# mapleCUx_large_226.net
KiCad netlist of a schematic drawn in EAGLE
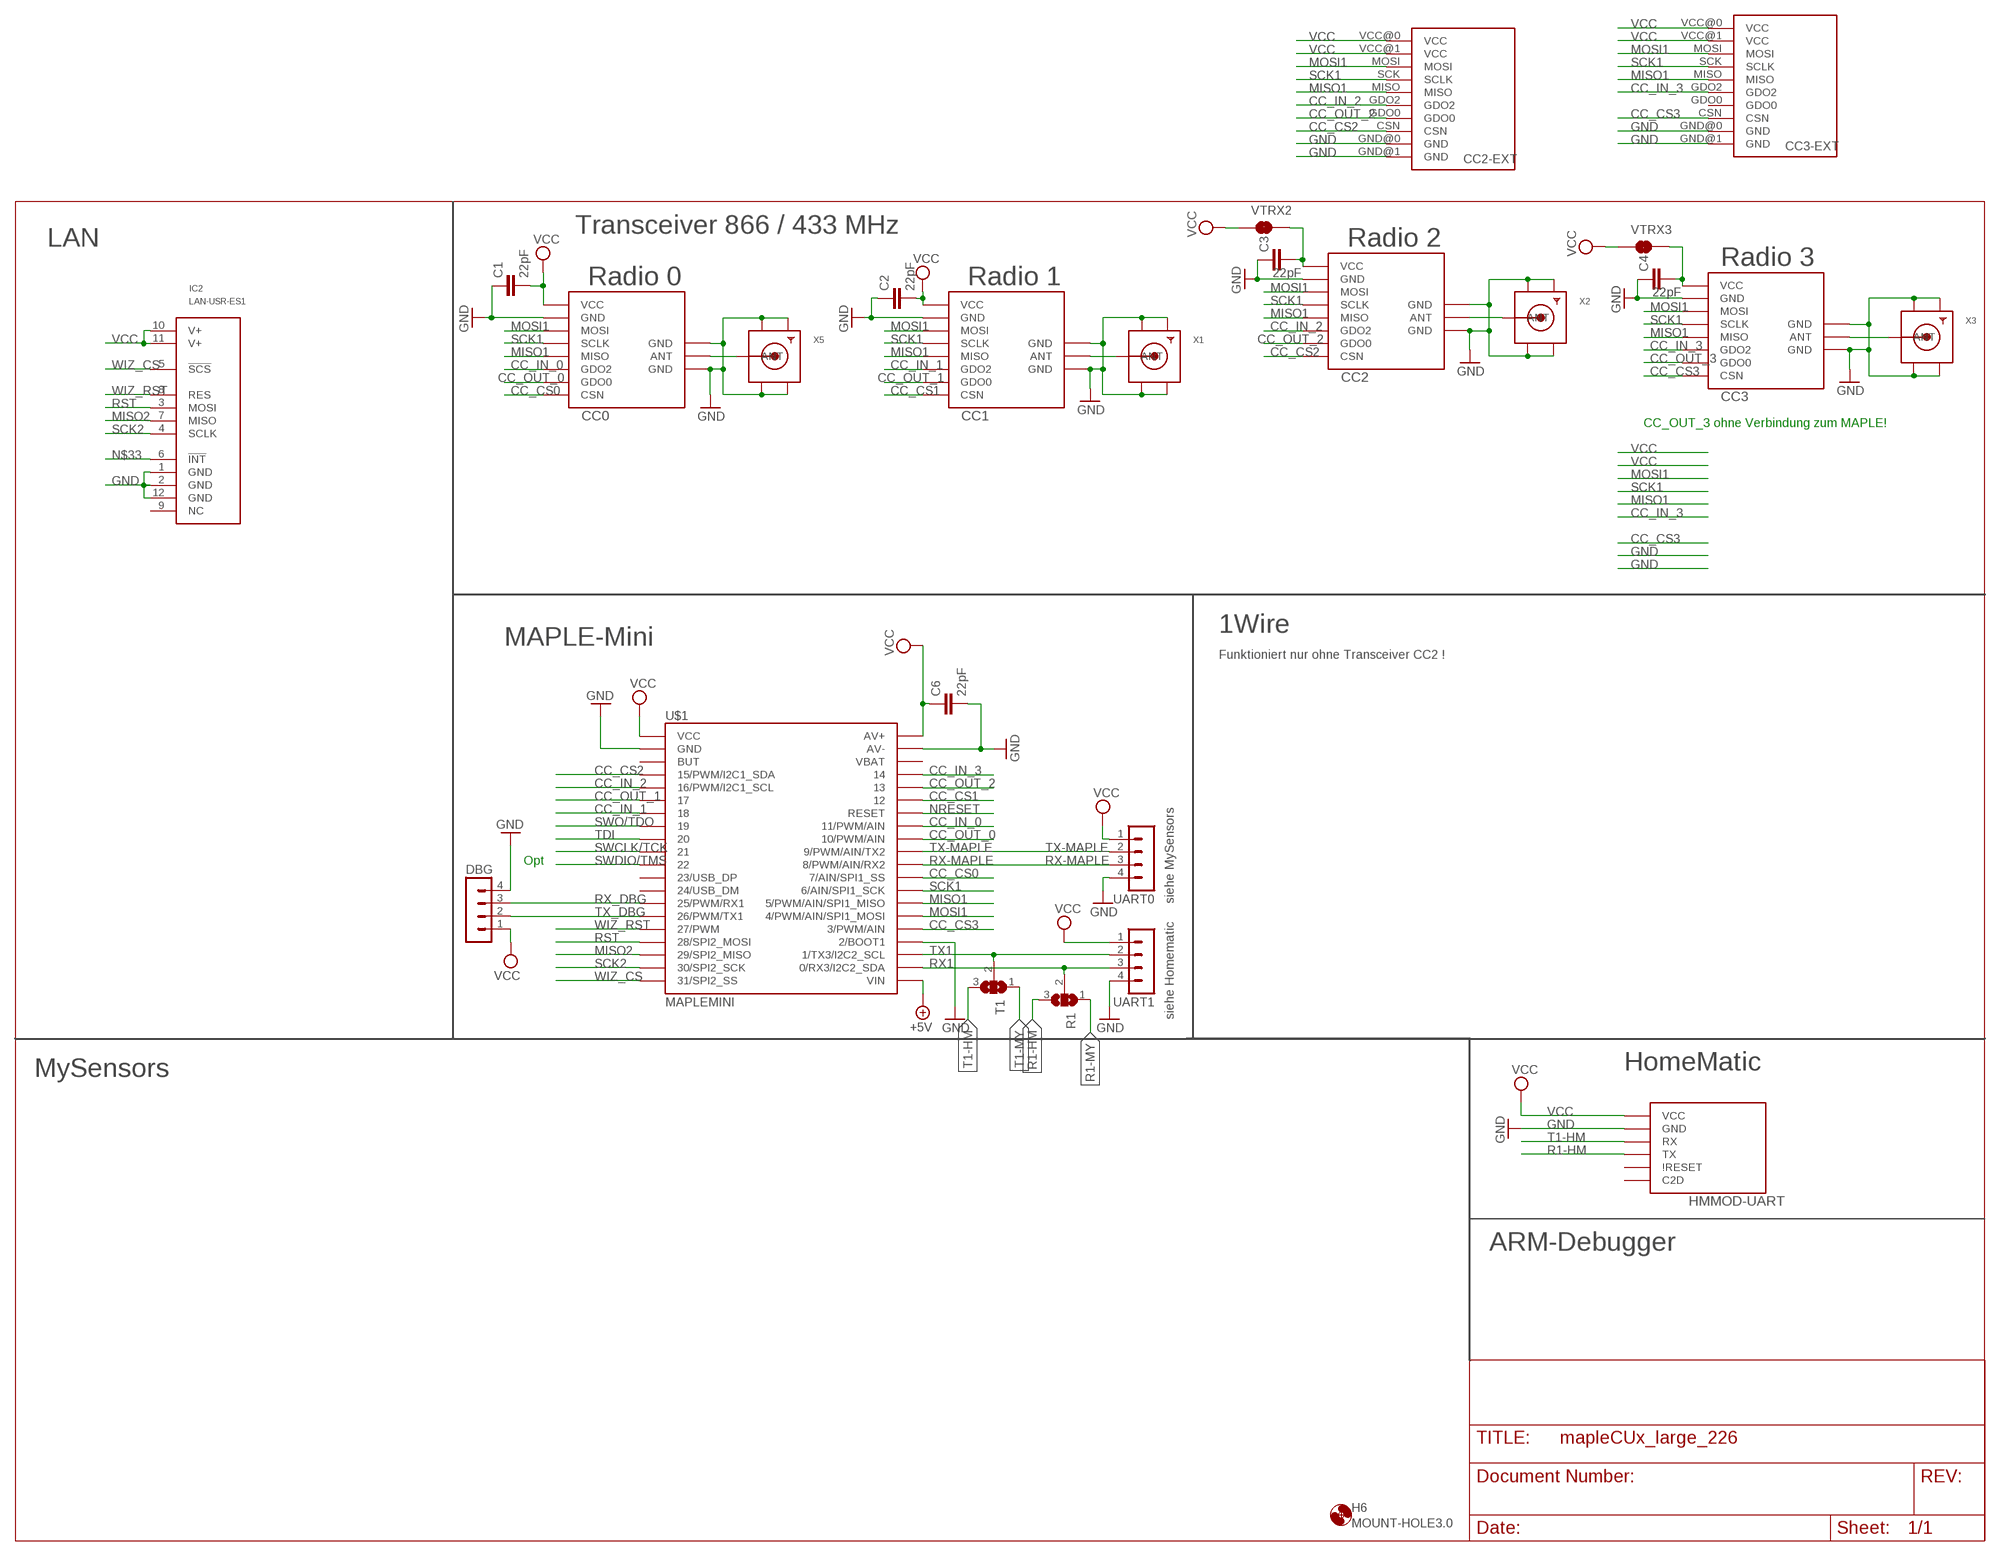
[diagram p0: schematic, sheet 1]

(export (version "E")
  (design (tool "Eeschema 10.0.6"))
  (components
    (comp (ref "C1")
      (value "22pF")
      (footprint "eagle-import:C0805")
      (libsource (lib "eagle-import") (part "C-EUC0805"))
    )
    (comp (ref "C2")
      (value "22pF")
      (footprint "eagle-import:C0805")
      (libsource (lib "eagle-import") (part "C-EUC0805"))
    )
    (comp (ref "C3")
      (value "22pF")
      (footprint "eagle-import:C0805")
      (libsource (lib "eagle-import") (part "C-EUC0805"))
    )
    (comp (ref "C4")
      (value "22pF")
      (footprint "eagle-import:C0805")
      (libsource (lib "eagle-import") (part "C-EUC0805"))
    )
    (comp (ref "C6")
      (value "22pF")
      (footprint "eagle-import:C0805")
      (libsource (lib "eagle-import") (part "C-EUC0805"))
    )
    (comp (ref "CC0")
      (value "CC1101")
      (footprint "eagle-import:CC1101_MODULE1_SMD")
      (libsource (lib "eagle-import") (part "CC1101_MODULE1SMD"))
    )
    (comp (ref "CC1")
      (value "CC1101_MODULE1SMD")
      (footprint "eagle-import:CC1101_MODULE1_SMD")
      (libsource (lib "eagle-import") (part "CC1101_MODULE1SMD"))
    )
    (comp (ref "CC2")
      (value "CC1101_MODULE1SMD")
      (footprint "eagle-import:CC1101_MODULE1_SMD")
      (libsource (lib "eagle-import") (part "CC1101_MODULE1SMD"))
    )
    (comp (ref "CC2-EXT")
      (value "CC1101_MODULE3_DIL")
      (footprint "eagle-import:CC1101_MODULE3_DIL")
      (libsource (lib "eagle-import") (part "CC1101_MODULE3_DIL"))
    )
    (comp (ref "CC3")
      (value "CC1101_MODULE1SMD")
      (footprint "eagle-import:CC1101_MODULE1_SMD")
      (libsource (lib "eagle-import") (part "CC1101_MODULE1SMD"))
    )
    (comp (ref "CC3-EXT")
      (value "CC1101_MODULE3_DIL")
      (footprint "eagle-import:CC1101_MODULE3_DIL")
      (libsource (lib "eagle-import") (part "CC1101_MODULE3_DIL"))
    )
    (comp (ref "DBG")
      (value "MA04-1")
      (footprint "eagle-import:MA04-1")
      (libsource (lib "eagle-import") (part "MA04-1"))
    )
    (comp (ref "H6")
      (value "MOUNT-HOLE3.0")
      (footprint "eagle-import:3,0")
      (libsource (lib "eagle-import") (part "MOUNT-HOLE3.0"))
    )
    (comp (ref "HMMOD-UART")
      (value "HM-MOD-UARTDIL")
      (footprint "eagle-import:HM-MOD-UART-DIL")
      (libsource (lib "eagle-import") (part "HM-MOD-UARTDIL"))
    )
    (comp (ref "IC2")
      (value "LAN-USR-ES1")
      (footprint "eagle-import:USR-ES1")
      (libsource (lib "eagle-import") (part "LAN-USR-ES1"))
    )
    (comp (ref "R1")
      (value "SJ2W")
      (footprint "eagle-import:SJ_2")
      (libsource (lib "eagle-import") (part "SJ2W"))
    )
    (comp (ref "T1")
      (value "SJ2W")
      (footprint "eagle-import:SJ_2")
      (libsource (lib "eagle-import") (part "SJ2W"))
    )
    (comp (ref "U$1")
      (value "MAPLEMINI")
      (footprint "eagle-import:20-DIP")
      (libsource (lib "eagle-import") (part "MAPLEMINI"))
    )
    (comp (ref "UART0")
      (value "MA04-1")
      (footprint "eagle-import:MA04-1")
      (libsource (lib "eagle-import") (part "MA04-1"))
    )
    (comp (ref "UART1")
      (value "MA04-1")
      (footprint "eagle-import:MA04-1")
      (libsource (lib "eagle-import") (part "MA04-1"))
    )
    (comp (ref "VTRX2")
      (value "JUMPER-SMT_2_NC_TRACE_SILK")
      (footprint "eagle-import:SMT-JUMPER_2_NC_TRACE_SILK")
      (libsource (lib "eagle-import") (part "JUMPER-SMT_2_NC_TRACE_SILK"))
    )
    (comp (ref "VTRX3")
      (value "JUMPER-SMT_2_NC_TRACE_SILK")
      (footprint "eagle-import:SMT-JUMPER_2_NC_TRACE_SILK")
      (libsource (lib "eagle-import") (part "JUMPER-SMT_2_NC_TRACE_SILK"))
    )
    (comp (ref "X1")
      (value "SMACONNECTOR_EDGE")
      (footprint "eagle-import:SMA_EDGELAUNCH")
      (libsource (lib "eagle-import") (part "SMACONNECTOR_EDGE"))
    )
    (comp (ref "X2")
      (value "SMACONNECTOR_EDGE")
      (footprint "eagle-import:SMA_EDGELAUNCH")
      (libsource (lib "eagle-import") (part "SMACONNECTOR_EDGE"))
    )
    (comp (ref "X3")
      (value "SMACONNECTOR_EDGE")
      (footprint "eagle-import:SMA_EDGELAUNCH")
      (libsource (lib "eagle-import") (part "SMACONNECTOR_EDGE"))
    )
    (comp (ref "X5")
      (value "SMACONNECTOR_EDGE")
      (footprint "eagle-import:SMA_EDGELAUNCH")
      (libsource (lib "eagle-import") (part "SMACONNECTOR_EDGE"))
    )
  )
  (nets
    (net (code "1") (name "+5V") (class "Default")
      (node (ref "U$1") (pin "21") (pinfunction "VIN_21") (pintype "bidirectional"))
    )
    (net (code "2") (name "/CC_CS0") (class "Default")
      (node (ref "CC0") (pin "CSN") (pinfunction "CSN_CSN") (pintype "bidirectional"))
      (node (ref "U$1") (pin "29") (pinfunction "7/AIN/SPI1_SS_29") (pintype "bidirectional"))
    )
    (net (code "3") (name "/CC_CS1") (class "Default")
      (node (ref "CC1") (pin "CSN") (pinfunction "CSN_CSN") (pintype "bidirectional"))
      (node (ref "U$1") (pin "35") (pinfunction "12_35") (pintype "bidirectional"))
    )
    (net (code "4") (name "/CC_CS2") (class "Default")
      (node (ref "CC2") (pin "CSN") (pinfunction "CSN_CSN") (pintype "bidirectional"))
      (node (ref "CC2-EXT") (pin "CSN") (pinfunction "CSN_CSN") (pintype "bidirectional"))
      (node (ref "U$1") (pin "4") (pinfunction "15/PWM/I2C1_SDA_4") (pintype "bidirectional"))
    )
    (net (code "5") (name "/CC_CS3") (class "Default")
      (node (ref "CC3") (pin "CSN") (pinfunction "CSN_CSN") (pintype "bidirectional"))
      (node (ref "CC3-EXT") (pin "CSN") (pinfunction "CSN_CSN") (pintype "bidirectional"))
      (node (ref "U$1") (pin "25") (pinfunction "3/PWM/AIN_25") (pintype "bidirectional"))
    )
    (net (code "6") (name "/CC_IN_0") (class "Default")
      (node (ref "CC0") (pin "GDO2") (pinfunction "GDO2_GDO2") (pintype "bidirectional"))
      (node (ref "U$1") (pin "33") (pinfunction "11/PWM/AIN_33") (pintype "bidirectional"))
    )
    (net (code "7") (name "/CC_IN_1") (class "Default")
      (node (ref "CC1") (pin "GDO2") (pinfunction "GDO2_GDO2") (pintype "bidirectional"))
      (node (ref "U$1") (pin "7") (pinfunction "18_7") (pintype "bidirectional"))
    )
    (net (code "8") (name "/CC_IN_2") (class "Default")
      (node (ref "CC2") (pin "GDO2") (pinfunction "GDO2_GDO2") (pintype "bidirectional"))
      (node (ref "CC2-EXT") (pin "GDO2") (pinfunction "GDO2_GDO2") (pintype "bidirectional"))
      (node (ref "U$1") (pin "5") (pinfunction "16/PWM/I2C1_SCL_5") (pintype "bidirectional"))
    )
    (net (code "9") (name "/CC_IN_3") (class "Default")
      (node (ref "CC3") (pin "GDO2") (pinfunction "GDO2_GDO2") (pintype "bidirectional"))
      (node (ref "CC3-EXT") (pin "GDO2") (pinfunction "GDO2_GDO2") (pintype "bidirectional"))
      (node (ref "U$1") (pin "37") (pinfunction "14_37") (pintype "bidirectional"))
    )
    (net (code "10") (name "/CC_OUT_0") (class "Default")
      (node (ref "CC0") (pin "GDO0") (pinfunction "GDO0_GDO0") (pintype "bidirectional"))
      (node (ref "U$1") (pin "32") (pinfunction "10/PWM/AIN_32") (pintype "bidirectional"))
    )
    (net (code "11") (name "/CC_OUT_1") (class "Default")
      (node (ref "CC1") (pin "GDO0") (pinfunction "GDO0_GDO0") (pintype "bidirectional"))
      (node (ref "U$1") (pin "6") (pinfunction "17_6") (pintype "bidirectional"))
    )
    (net (code "12") (name "/CC_OUT_2") (class "Default")
      (node (ref "CC2") (pin "GDO0") (pinfunction "GDO0_GDO0") (pintype "bidirectional"))
      (node (ref "CC2-EXT") (pin "GDO0") (pinfunction "GDO0_GDO0") (pintype "bidirectional"))
      (node (ref "U$1") (pin "36") (pinfunction "13_36") (pintype "bidirectional"))
    )
    (net (code "13") (name "/CC_OUT_3") (class "Default")
      (node (ref "CC3") (pin "GDO0") (pinfunction "GDO0_GDO0") (pintype "bidirectional"))
    )
    (net (code "14") (name "/MISO1") (class "Default")
      (node (ref "CC0") (pin "MISO") (pinfunction "MISO_MISO") (pintype "bidirectional"))
      (node (ref "CC1") (pin "MISO") (pinfunction "MISO_MISO") (pintype "bidirectional"))
      (node (ref "CC2") (pin "MISO") (pinfunction "MISO_MISO") (pintype "bidirectional"))
      (node (ref "CC2-EXT") (pin "MISO") (pinfunction "MISO_MISO") (pintype "bidirectional"))
      (node (ref "CC3") (pin "MISO") (pinfunction "MISO_MISO") (pintype "bidirectional"))
      (node (ref "CC3-EXT") (pin "MISO") (pinfunction "MISO_MISO") (pintype "bidirectional"))
      (node (ref "U$1") (pin "27") (pinfunction "5/PWM/AIN/SPI1_MISO_27") (pintype "bidirectional"))
    )
    (net (code "15") (name "/MISO2") (class "Default")
      (node (ref "IC2") (pin "7") (pinfunction "MISO_7") (pintype "bidirectional"))
      (node (ref "U$1") (pin "18") (pinfunction "29/SPI2_MISO_18") (pintype "bidirectional"))
    )
    (net (code "16") (name "/MOSI1") (class "Default")
      (node (ref "CC0") (pin "MOSI") (pinfunction "MOSI_MOSI") (pintype "bidirectional"))
      (node (ref "CC1") (pin "MOSI") (pinfunction "MOSI_MOSI") (pintype "bidirectional"))
      (node (ref "CC2") (pin "MOSI") (pinfunction "MOSI_MOSI") (pintype "bidirectional"))
      (node (ref "CC2-EXT") (pin "MOSI") (pinfunction "MOSI_MOSI") (pintype "bidirectional"))
      (node (ref "CC3") (pin "MOSI") (pinfunction "MOSI_MOSI") (pintype "bidirectional"))
      (node (ref "CC3-EXT") (pin "MOSI") (pinfunction "MOSI_MOSI") (pintype "bidirectional"))
      (node (ref "U$1") (pin "26") (pinfunction "4/PWM/AIN/SPI1_MOSI_26") (pintype "bidirectional"))
    )
    (net (code "17") (name "/N$33") (class "Default")
      (node (ref "IC2") (pin "6") (pinfunction "~{INT}_6") (pintype "output"))
    )
    (net (code "18") (name "/NRESET") (class "Default")
      (node (ref "U$1") (pin "34") (pinfunction "RESET_34") (pintype "bidirectional"))
    )
    (net (code "19") (name "/RST") (class "Default")
      (node (ref "IC2") (pin "3") (pinfunction "MOSI_3") (pintype "bidirectional"))
      (node (ref "U$1") (pin "17") (pinfunction "28/SPI2_MOSI_17") (pintype "bidirectional"))
    )
    (net (code "20") (name "/RX-MAPLE") (class "Default")
      (node (ref "U$1") (pin "30") (pinfunction "8/PWM/AIN/RX2_30") (pintype "bidirectional"))
      (node (ref "UART0") (pin "3") (pinfunction "3_3") (pintype "passive"))
    )
    (net (code "21") (name "/RX1") (class "Default")
      (node (ref "R1") (pin "2") (pinfunction "2_2") (pintype "passive"))
      (node (ref "U$1") (pin "22") (pinfunction "0/RX3/I2C2_SDA_22") (pintype "bidirectional"))
      (node (ref "UART1") (pin "3") (pinfunction "3_3") (pintype "passive"))
    )
    (net (code "22") (name "/RX_DBG") (class "Default")
      (node (ref "DBG") (pin "3") (pinfunction "3_3") (pintype "passive"))
      (node (ref "U$1") (pin "14") (pinfunction "25/PWM/RX1_14") (pintype "bidirectional"))
    )
    (net (code "23") (name "/SCK1") (class "Default")
      (node (ref "CC0") (pin "SCLK") (pinfunction "SCLK_SCLK") (pintype "bidirectional"))
      (node (ref "CC1") (pin "SCLK") (pinfunction "SCLK_SCLK") (pintype "bidirectional"))
      (node (ref "CC2") (pin "SCLK") (pinfunction "SCLK_SCLK") (pintype "bidirectional"))
      (node (ref "CC2-EXT") (pin "SCK") (pinfunction "SCLK_SCK") (pintype "bidirectional"))
      (node (ref "CC3") (pin "SCLK") (pinfunction "SCLK_SCLK") (pintype "bidirectional"))
      (node (ref "CC3-EXT") (pin "SCK") (pinfunction "SCLK_SCK") (pintype "bidirectional"))
      (node (ref "U$1") (pin "28") (pinfunction "6/AIN/SPI1_SCK_28") (pintype "bidirectional"))
    )
    (net (code "24") (name "/SCK2") (class "Default")
      (node (ref "IC2") (pin "4") (pinfunction "SCLK_4") (pintype "input"))
      (node (ref "U$1") (pin "19") (pinfunction "30/SPI2_SCK_19") (pintype "bidirectional"))
    )
    (net (code "25") (name "/SWCLK{slash}TCK") (class "Default")
      (node (ref "U$1") (pin "10") (pinfunction "21_10") (pintype "bidirectional"))
    )
    (net (code "26") (name "/SWDIO{slash}TMS") (class "Default")
      (node (ref "U$1") (pin "11") (pinfunction "22_11") (pintype "bidirectional"))
    )
    (net (code "27") (name "/SWO{slash}TDO") (class "Default")
      (node (ref "U$1") (pin "8") (pinfunction "19_8") (pintype "bidirectional"))
    )
    (net (code "28") (name "/TDI") (class "Default")
      (node (ref "U$1") (pin "9") (pinfunction "20_9") (pintype "bidirectional"))
    )
    (net (code "29") (name "/TX-MAPLE") (class "Default")
      (node (ref "U$1") (pin "31") (pinfunction "9/PWM/AIN/TX2_31") (pintype "bidirectional"))
      (node (ref "UART0") (pin "2") (pinfunction "2_2") (pintype "passive"))
    )
    (net (code "30") (name "/TX1") (class "Default")
      (node (ref "T1") (pin "2") (pinfunction "2_2") (pintype "passive"))
      (node (ref "U$1") (pin "23") (pinfunction "1/TX3/I2C2_SCL_23") (pintype "bidirectional"))
      (node (ref "UART1") (pin "2") (pinfunction "2_2") (pintype "passive"))
    )
    (net (code "31") (name "/TX_DBG") (class "Default")
      (node (ref "DBG") (pin "2") (pinfunction "2_2") (pintype "passive"))
      (node (ref "U$1") (pin "15") (pinfunction "26/PWM/TX1_15") (pintype "bidirectional"))
    )
    (net (code "32") (name "/WIZ_CS") (class "Default")
      (node (ref "IC2") (pin "5") (pinfunction "~{SCS}_5") (pintype "input"))
      (node (ref "U$1") (pin "20") (pinfunction "31/SPI2_SS_20") (pintype "bidirectional"))
    )
    (net (code "33") (name "/WIZ_RST") (class "Default")
      (node (ref "IC2") (pin "8") (pinfunction "RES_8") (pintype "input"))
      (node (ref "U$1") (pin "16") (pinfunction "27/PWM_16") (pintype "bidirectional"))
    )
    (net (code "34") (name "GND") (class "Default")
      (node (ref "C1") (pin "1") (pinfunction "1_1") (pintype "passive"))
      (node (ref "C2") (pin "1") (pinfunction "1_1") (pintype "passive"))
      (node (ref "C3") (pin "1") (pinfunction "1_1") (pintype "passive"))
      (node (ref "C4") (pin "1") (pinfunction "1_1") (pintype "passive"))
      (node (ref "C6") (pin "2") (pinfunction "2_2") (pintype "passive"))
      (node (ref "CC0") (pin "GND@0") (pinfunction "GND_GND@0") (pintype "power_in"))
      (node (ref "CC0") (pin "GND@1") (pinfunction "GND_GND@1") (pintype "power_in"))
      (node (ref "CC0") (pin "GND@2") (pinfunction "GND_GND@2") (pintype "power_in"))
      (node (ref "CC1") (pin "GND@0") (pinfunction "GND_GND@0") (pintype "power_in"))
      (node (ref "CC1") (pin "GND@1") (pinfunction "GND_GND@1") (pintype "power_in"))
      (node (ref "CC1") (pin "GND@2") (pinfunction "GND_GND@2") (pintype "power_in"))
      (node (ref "CC2") (pin "GND@0") (pinfunction "GND_GND@0") (pintype "power_in"))
      (node (ref "CC2") (pin "GND@1") (pinfunction "GND_GND@1") (pintype "power_in"))
      (node (ref "CC2") (pin "GND@2") (pinfunction "GND_GND@2") (pintype "power_in"))
      (node (ref "CC2-EXT") (pin "GND@0") (pinfunction "GND_GND@0") (pintype "power_in"))
      (node (ref "CC2-EXT") (pin "GND@1") (pinfunction "GND_GND@1") (pintype "power_in"))
      (node (ref "CC3") (pin "GND@0") (pinfunction "GND_GND@0") (pintype "power_in"))
      (node (ref "CC3") (pin "GND@1") (pinfunction "GND_GND@1") (pintype "power_in"))
      (node (ref "CC3") (pin "GND@2") (pinfunction "GND_GND@2") (pintype "power_in"))
      (node (ref "CC3-EXT") (pin "GND@0") (pinfunction "GND_GND@0") (pintype "power_in"))
      (node (ref "CC3-EXT") (pin "GND@1") (pinfunction "GND_GND@1") (pintype "power_in"))
      (node (ref "DBG") (pin "4") (pinfunction "4_4") (pintype "passive"))
      (node (ref "HMMOD-UART") (pin "2") (pinfunction "GND_2") (pintype "power_in"))
      (node (ref "IC2") (pin "1") (pinfunction "GND_1") (pintype "power_in"))
      (node (ref "IC2") (pin "12") (pinfunction "GND_12") (pintype "power_in"))
      (node (ref "IC2") (pin "2") (pinfunction "GND_2") (pintype "power_in"))
      (node (ref "U$1") (pin "2") (pinfunction "GND_2") (pintype "bidirectional"))
      (node (ref "U$1") (pin "24") (pinfunction "2/BOOT1_24") (pintype "bidirectional"))
      (node (ref "U$1") (pin "39") (pinfunction "AV-_39") (pintype "bidirectional"))
      (node (ref "UART0") (pin "4") (pinfunction "4_4") (pintype "passive"))
      (node (ref "UART1") (pin "4") (pinfunction "4_4") (pintype "passive"))
      (node (ref "X1") (pin "GND@1") (pinfunction "GND4_GND@1") (pintype "power_in"))
      (node (ref "X1") (pin "GND@2") (pinfunction "GND3_GND@2") (pintype "power_in"))
      (node (ref "X1") (pin "GND@3") (pinfunction "GND2_GND@3") (pintype "power_in"))
      (node (ref "X1") (pin "GND@4") (pinfunction "GND1_GND@4") (pintype "power_in"))
      (node (ref "X2") (pin "GND@1") (pinfunction "GND4_GND@1") (pintype "power_in"))
      (node (ref "X2") (pin "GND@2") (pinfunction "GND3_GND@2") (pintype "power_in"))
      (node (ref "X2") (pin "GND@3") (pinfunction "GND2_GND@3") (pintype "power_in"))
      (node (ref "X2") (pin "GND@4") (pinfunction "GND1_GND@4") (pintype "power_in"))
      (node (ref "X3") (pin "GND@1") (pinfunction "GND4_GND@1") (pintype "power_in"))
      (node (ref "X3") (pin "GND@2") (pinfunction "GND3_GND@2") (pintype "power_in"))
      (node (ref "X3") (pin "GND@3") (pinfunction "GND2_GND@3") (pintype "power_in"))
      (node (ref "X3") (pin "GND@4") (pinfunction "GND1_GND@4") (pintype "power_in"))
      (node (ref "X5") (pin "GND@1") (pinfunction "GND4_GND@1") (pintype "power_in"))
      (node (ref "X5") (pin "GND@2") (pinfunction "GND3_GND@2") (pintype "power_in"))
      (node (ref "X5") (pin "GND@3") (pinfunction "GND2_GND@3") (pintype "power_in"))
      (node (ref "X5") (pin "GND@4") (pinfunction "GND1_GND@4") (pintype "power_in"))
    )
    (net (code "35") (name "Net-(C3-Pad2)") (class "Default")
      (node (ref "C3") (pin "2") (pinfunction "2_2") (pintype "passive"))
      (node (ref "CC2") (pin "VCC") (pinfunction "VCC_VCC") (pintype "power_in"))
      (node (ref "VTRX2") (pin "2") (pinfunction "2_2") (pintype "passive"))
    )
    (net (code "36") (name "Net-(C4-Pad2)") (class "Default")
      (node (ref "C4") (pin "2") (pinfunction "2_2") (pintype "passive"))
      (node (ref "CC3") (pin "VCC") (pinfunction "VCC_VCC") (pintype "power_in"))
      (node (ref "VTRX3") (pin "2") (pinfunction "2_2") (pintype "passive"))
    )
    (net (code "37") (name "Net-(X1-ANT)") (class "Default")
      (node (ref "CC1") (pin "ANT") (pinfunction "ANT_ANT") (pintype "output"))
      (node (ref "X1") (pin "P") (pinfunction "ANT_P") (pintype "bidirectional"))
    )
    (net (code "38") (name "Net-(X2-ANT)") (class "Default")
      (node (ref "CC2") (pin "ANT") (pinfunction "ANT_ANT") (pintype "output"))
      (node (ref "X2") (pin "P") (pinfunction "ANT_P") (pintype "bidirectional"))
    )
    (net (code "39") (name "Net-(X3-ANT)") (class "Default")
      (node (ref "CC3") (pin "ANT") (pinfunction "ANT_ANT") (pintype "output"))
      (node (ref "X3") (pin "P") (pinfunction "ANT_P") (pintype "bidirectional"))
    )
    (net (code "40") (name "Net-(X5-ANT)") (class "Default")
      (node (ref "CC0") (pin "ANT") (pinfunction "ANT_ANT") (pintype "output"))
      (node (ref "X5") (pin "P") (pinfunction "ANT_P") (pintype "bidirectional"))
    )
    (net (code "41") (name "R1-HM") (class "Default")
      (node (ref "HMMOD-UART") (pin "5") (pinfunction "TX_5") (pintype "bidirectional"))
      (node (ref "R1") (pin "3") (pinfunction "3_3") (pintype "passive"))
    )
    (net (code "42") (name "R1-MY") (class "Default")
      (node (ref "R1") (pin "1") (pinfunction "1_1") (pintype "passive"))
    )
    (net (code "43") (name "T1-HM") (class "Default")
      (node (ref "HMMOD-UART") (pin "6") (pinfunction "RX_6") (pintype "bidirectional"))
      (node (ref "T1") (pin "3") (pinfunction "3_3") (pintype "passive"))
    )
    (net (code "44") (name "T1-MY") (class "Default")
      (node (ref "T1") (pin "1") (pinfunction "1_1") (pintype "passive"))
    )
    (net (code "45") (name "VCC") (class "Default")
      (node (ref "C1") (pin "2") (pinfunction "2_2") (pintype "passive"))
      (node (ref "C2") (pin "2") (pinfunction "2_2") (pintype "passive"))
      (node (ref "C6") (pin "1") (pinfunction "1_1") (pintype "passive"))
      (node (ref "CC0") (pin "VCC") (pinfunction "VCC_VCC") (pintype "power_in"))
      (node (ref "CC1") (pin "VCC") (pinfunction "VCC_VCC") (pintype "power_in"))
      (node (ref "CC2-EXT") (pin "VCC@0") (pinfunction "VCC_VCC@0") (pintype "power_in"))
      (node (ref "CC2-EXT") (pin "VCC@1") (pinfunction "VCC_VCC@1") (pintype "power_in"))
      (node (ref "CC3-EXT") (pin "VCC@0") (pinfunction "VCC_VCC@0") (pintype "power_in"))
      (node (ref "CC3-EXT") (pin "VCC@1") (pinfunction "VCC_VCC@1") (pintype "power_in"))
      (node (ref "DBG") (pin "1") (pinfunction "1_1") (pintype "passive"))
      (node (ref "HMMOD-UART") (pin "1") (pinfunction "VCC_1") (pintype "power_in"))
      (node (ref "IC2") (pin "10") (pinfunction "V+_10") (pintype "power_in"))
      (node (ref "IC2") (pin "11") (pinfunction "V+_11") (pintype "power_in"))
      (node (ref "U$1") (pin "1") (pinfunction "VCC_1") (pintype "bidirectional"))
      (node (ref "U$1") (pin "40") (pinfunction "AV+_40") (pintype "bidirectional"))
      (node (ref "UART0") (pin "1") (pinfunction "1_1") (pintype "passive"))
      (node (ref "UART1") (pin "1") (pinfunction "1_1") (pintype "passive"))
      (node (ref "VTRX2") (pin "1") (pinfunction "1_1") (pintype "passive"))
      (node (ref "VTRX3") (pin "1") (pinfunction "1_1") (pintype "passive"))
    )
    (net (code "46") (name "unconnected-(CC3-EXT-PadGDO0)") (class "Default")
      (node (ref "CC3-EXT") (pin "GDO0") (pinfunction "GDO0_GDO0") (pintype "bidirectional"))
    )
    (net (code "47") (name "unconnected-(HMMOD-UART-C2D-Pad3)") (class "Default")
      (node (ref "HMMOD-UART") (pin "3") (pinfunction "C2D_3") (pintype "bidirectional"))
    )
    (net (code "48") (name "unconnected-(HMMOD-UART-\\~{RESET}-Pad4)") (class "Default")
      (node (ref "HMMOD-UART") (pin "4") (pinfunction "\\~{RESET}_4") (pintype "bidirectional"))
    )
    (net (code "49") (name "unconnected-(IC2-NC-Pad9)") (class "Default")
      (node (ref "IC2") (pin "9") (pinfunction "NC_9") (pintype "no_connect"))
    )
    (net (code "50") (name "unconnected-(U$1-23{slash}USB_DP-Pad12)") (class "Default")
      (node (ref "U$1") (pin "12") (pinfunction "23/USB_DP_12") (pintype "bidirectional"))
    )
    (net (code "51") (name "unconnected-(U$1-24{slash}USB_DM-Pad13)") (class "Default")
      (node (ref "U$1") (pin "13") (pinfunction "24/USB_DM_13") (pintype "bidirectional"))
    )
    (net (code "52") (name "unconnected-(U$1-BUT-Pad3)") (class "Default")
      (node (ref "U$1") (pin "3") (pinfunction "BUT_3") (pintype "bidirectional"))
    )
    (net (code "53") (name "unconnected-(U$1-VBAT-Pad38)") (class "Default")
      (node (ref "U$1") (pin "38") (pinfunction "VBAT_38") (pintype "bidirectional"))
    )
  )
)
